# UltrasonicSensor.net
KiCad netlist of a schematic drawn in EAGLE
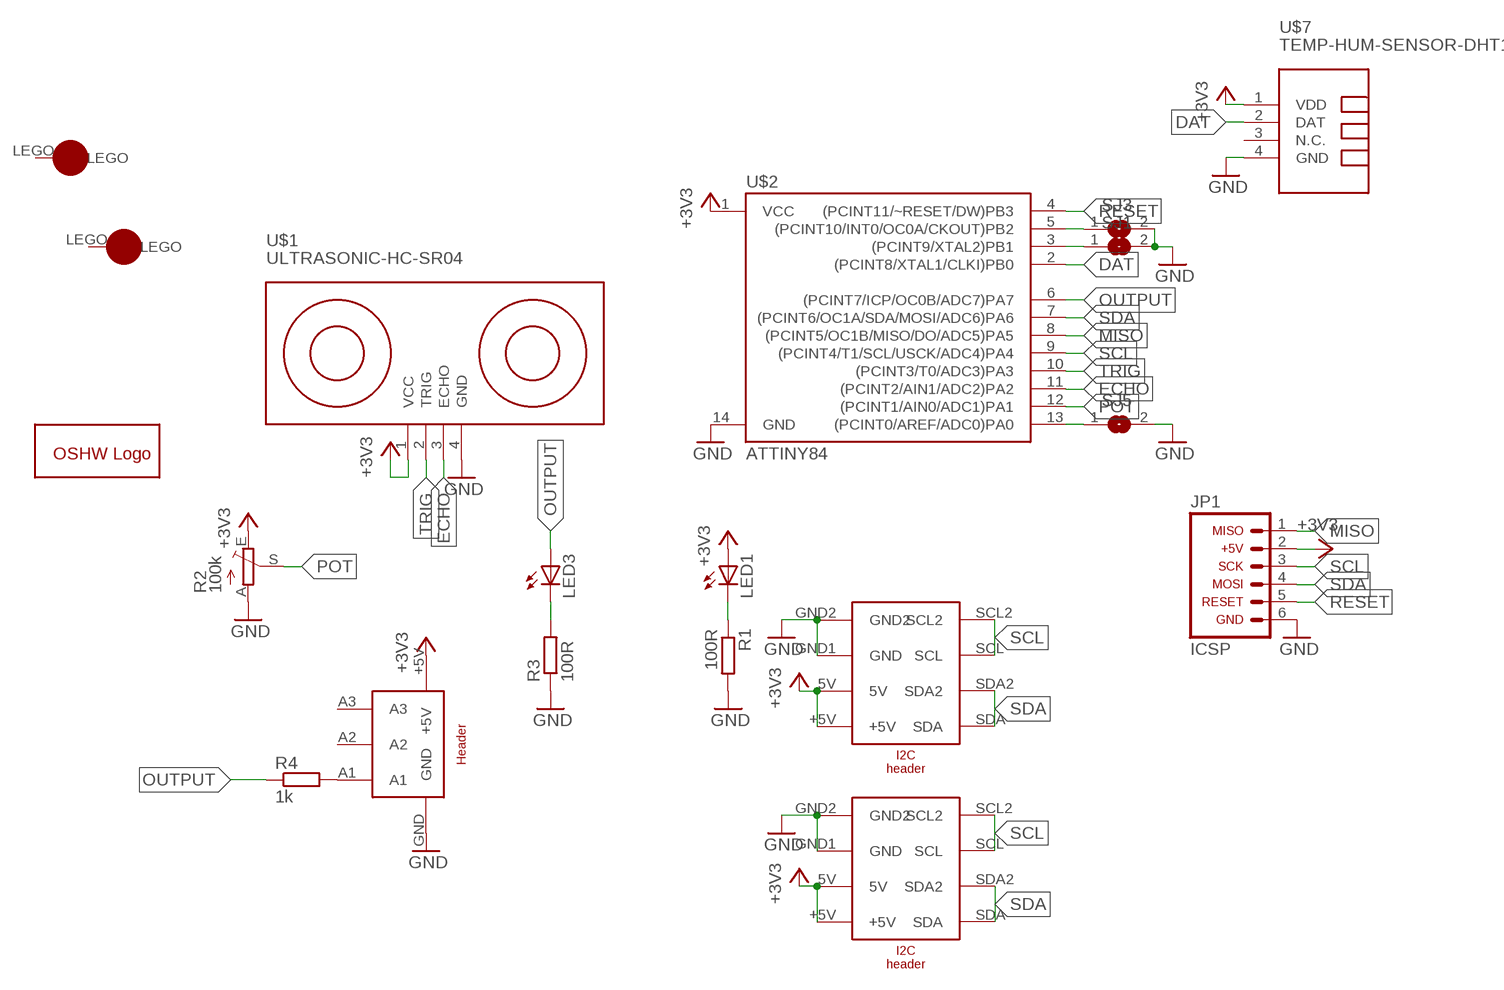
[diagram p0: schematic, sheet 1]

(export (version "E")
  (design (tool "Eeschema 10.0.6"))
  (components
    (comp (ref "JP1")
      (value "ICSP_HEADER")
      (footprint "eagle-import:ICSP_HEADER")
      (libsource (lib "eagle-import") (part "ICSP_HEADER"))
    )
    (comp (ref "LED1")
      (value "LEDCHIPLED_1206")
      (footprint "eagle-import:CHIPLED_1206")
      (libsource (lib "eagle-import") (part "LEDCHIPLED_1206"))
    )
    (comp (ref "LED3")
      (value "LEDCHIPLED_1206")
      (footprint "eagle-import:CHIPLED_1206")
      (libsource (lib "eagle-import") (part "LEDCHIPLED_1206"))
    )
    (comp (ref "R1")
      (value "100R")
      (footprint "eagle-import:M1206")
      (libsource (lib "eagle-import") (part "R-EU_M1206"))
    )
    (comp (ref "R2")
      (value "100k")
      (footprint "eagle-import:B64Y")
      (libsource (lib "eagle-import") (part "TRIM_EU-B64Y"))
    )
    (comp (ref "R3")
      (value "100R")
      (footprint "eagle-import:M1206")
      (libsource (lib "eagle-import") (part "R-EU_M1206"))
    )
    (comp (ref "R4")
      (value "1k")
      (footprint "eagle-import:M1206")
      (libsource (lib "eagle-import") (part "R-EU_M1206"))
    )
    (comp (ref "SJ1") (value "SJ") (footprint "eagle-import:SJ") (libsource (lib "eagle-import") (part "SJ")))
    (comp (ref "SJ3") (value "SJ") (footprint "eagle-import:SJ") (libsource (lib "eagle-import") (part "SJ")))
    (comp (ref "SJ5") (value "SJ") (footprint "eagle-import:SJ") (libsource (lib "eagle-import") (part "SJ")))
    (comp (ref "U$1")
      (value "ULTRASONIC-HC-SR04")
      (footprint "eagle-import:ULTRASONIC-HC-SR04")
      (libsource (lib "eagle-import") (part "ULTRASONIC-HC-SR04"))
    )
    (comp (ref "U$2")
      (value "ATTINY84")
      (footprint "eagle-import:SO14")
      (libsource (lib "eagle-import") (part "ATTINY84"))
    )
    (comp (ref "U$3")
      (value "I2C_HEADER")
      (footprint "eagle-import:I2_HEADER")
      (libsource (lib "eagle-import") (part "I2C_HEADER"))
    )
    (comp (ref "U$4")
      (value "I2C_HEADER")
      (footprint "eagle-import:I2_HEADER")
      (libsource (lib "eagle-import") (part "I2C_HEADER"))
    )
    (comp (ref "U$5")
      (value "OPENSOURCE")
      (footprint "eagle-import:OSHW_5MM")
      (libsource (lib "eagle-import") (part "OPENSOURCE"))
    )
    (comp (ref "U$6")
      (value "CONNECTOR_1X5")
      (footprint "eagle-import:CONNECTOR_1X5")
      (libsource (lib "eagle-import") (part "CONNECTOR_1X5"))
    )
    (comp (ref "U$7")
      (value "TEMP-HUM-SENSOR-DHT11")
      (footprint "eagle-import:TEMP-HUM-SENSOR-DHT11")
      (libsource (lib "eagle-import") (part "TEMP-HUM-SENSOR-DHT11"))
    )
    (comp (ref "U$8")
      (value "LEGO-1X1")
      (footprint "eagle-import:LEGO-1X1")
      (libsource (lib "eagle-import") (part "LEGO-1X1"))
    )
    (comp (ref "U$9")
      (value "LEGO-1X1")
      (footprint "eagle-import:LEGO-1X1")
      (libsource (lib "eagle-import") (part "LEGO-1X1"))
    )
  )
  (nets
    (net (code "1") (name "+3V3") (class "Default")
      (node (ref "JP1") (pin "2") (pinfunction "2_2") (pintype "passive"))
      (node (ref "LED1") (pin "A") (pinfunction "A_A") (pintype "passive"))
      (node (ref "R2") (pin "E") (pinfunction "E_E") (pintype "passive"))
      (node (ref "U$1") (pin "1") (pinfunction "VCC_1") (pintype "power_in"))
      (node (ref "U$2") (pin "1") (pinfunction "VCC_1") (pintype "bidirectional"))
      (node (ref "U$3") (pin "+5V") (pinfunction "+5V_+5V") (pintype "bidirectional"))
      (node (ref "U$3") (pin "5V") (pinfunction "5V_5V") (pintype "bidirectional"))
      (node (ref "U$4") (pin "+5V") (pinfunction "+5V_+5V") (pintype "bidirectional"))
      (node (ref "U$4") (pin "5V") (pinfunction "5V_5V") (pintype "bidirectional"))
      (node (ref "U$6") (pin "+5V") (pinfunction "+5V_+5V") (pintype "bidirectional"))
      (node (ref "U$7") (pin "1") (pinfunction "VDD_1") (pintype "power_in"))
    )
    (net (code "2") (name "DAT") (class "Default")
      (node (ref "U$2") (pin "2") (pinfunction "(PCINT8/XTAL1/CLKI)PB0_2") (pintype "bidirectional"))
      (node (ref "U$7") (pin "2") (pinfunction "DAT_2") (pintype "bidirectional"))
    )
    (net (code "3") (name "ECHO") (class "Default")
      (node (ref "U$1") (pin "3") (pinfunction "ECHO_3") (pintype "output"))
      (node (ref "U$2") (pin "11") (pinfunction "(PCINT2/AIN1/ADC2)PA2_11") (pintype "bidirectional"))
    )
    (net (code "4") (name "GND") (class "Default")
      (node (ref "JP1") (pin "6") (pinfunction "6_6") (pintype "passive"))
      (node (ref "R1") (pin "2") (pinfunction "2_2") (pintype "passive"))
      (node (ref "R2") (pin "A") (pinfunction "A_A") (pintype "passive"))
      (node (ref "R3") (pin "1") (pinfunction "1_1") (pintype "passive"))
      (node (ref "SJ1") (pin "2") (pinfunction "2_2") (pintype "passive"))
      (node (ref "SJ3") (pin "2") (pinfunction "2_2") (pintype "passive"))
      (node (ref "SJ5") (pin "2") (pinfunction "2_2") (pintype "passive"))
      (node (ref "U$1") (pin "4") (pinfunction "GND_4") (pintype "power_in"))
      (node (ref "U$2") (pin "14") (pinfunction "GND_14") (pintype "bidirectional"))
      (node (ref "U$3") (pin "GND1") (pinfunction "GND_GND1") (pintype "bidirectional"))
      (node (ref "U$3") (pin "GND2") (pinfunction "GND2_GND2") (pintype "bidirectional"))
      (node (ref "U$4") (pin "GND1") (pinfunction "GND_GND1") (pintype "bidirectional"))
      (node (ref "U$4") (pin "GND2") (pinfunction "GND2_GND2") (pintype "bidirectional"))
      (node (ref "U$6") (pin "GND") (pinfunction "GND_GND") (pintype "bidirectional"))
      (node (ref "U$7") (pin "4") (pinfunction "GND_4") (pintype "power_in"))
    )
    (net (code "5") (name "MISO") (class "Default")
      (node (ref "JP1") (pin "1") (pinfunction "1_1") (pintype "passive"))
      (node (ref "U$2") (pin "8") (pinfunction "(PCINT5/OC1B/MISO/DO/ADC5)PA5_8") (pintype "bidirectional"))
    )
    (net (code "6") (name "Net-(LED1-PadC)") (class "Default")
      (node (ref "LED1") (pin "C") (pinfunction "C_C") (pintype "passive"))
      (node (ref "R1") (pin "1") (pinfunction "1_1") (pintype "passive"))
    )
    (net (code "7") (name "Net-(LED3-PadC)") (class "Default")
      (node (ref "LED3") (pin "C") (pinfunction "C_C") (pintype "passive"))
      (node (ref "R3") (pin "2") (pinfunction "2_2") (pintype "passive"))
    )
    (net (code "8") (name "Net-(R4-Pad2)") (class "Default")
      (node (ref "R4") (pin "2") (pinfunction "2_2") (pintype "passive"))
      (node (ref "U$6") (pin "A1") (pinfunction "A1_A1") (pintype "bidirectional"))
    )
    (net (code "9") (name "Net-(U$2-(PCINT0{slash}AREF{slash}ADC0)PA0)") (class "Default")
      (node (ref "SJ5") (pin "1") (pinfunction "1_1") (pintype "passive"))
      (node (ref "U$2") (pin "13") (pinfunction "(PCINT0/AREF/ADC0)PA0_13") (pintype "bidirectional"))
    )
    (net (code "10") (name "Net-(U$2-(PCINT9{slash}XTAL2)PB1)") (class "Default")
      (node (ref "SJ1") (pin "1") (pinfunction "1_1") (pintype "passive"))
      (node (ref "U$2") (pin "3") (pinfunction "(PCINT9/XTAL2)PB1_3") (pintype "bidirectional"))
    )
    (net (code "11") (name "Net-(U$2-(PCINT10{slash}INT0{slash}OC0A{slash}CKOUT)PB2)") (class "Default")
      (node (ref "SJ3") (pin "1") (pinfunction "1_1") (pintype "passive"))
      (node (ref "U$2") (pin "5") (pinfunction "(PCINT10/INT0/OC0A/CKOUT)PB2_5") (pintype "bidirectional"))
    )
    (net (code "12") (name "OUTPUT") (class "Default")
      (node (ref "LED3") (pin "A") (pinfunction "A_A") (pintype "passive"))
      (node (ref "R4") (pin "1") (pinfunction "1_1") (pintype "passive"))
      (node (ref "U$2") (pin "6") (pinfunction "(PCINT7/ICP/OC0B/ADC7)PA7_6") (pintype "bidirectional"))
    )
    (net (code "13") (name "POT") (class "Default")
      (node (ref "R2") (pin "S") (pinfunction "S_S") (pintype "passive"))
      (node (ref "U$2") (pin "12") (pinfunction "(PCINT1/AIN0/ADC1)PA1_12") (pintype "bidirectional"))
    )
    (net (code "14") (name "RESET") (class "Default")
      (node (ref "JP1") (pin "5") (pinfunction "5_5") (pintype "passive"))
      (node (ref "U$2") (pin "4") (pinfunction "(PCINT11/~{RESET/DW})PB3_4") (pintype "bidirectional"))
    )
    (net (code "15") (name "SCL") (class "Default")
      (node (ref "JP1") (pin "3") (pinfunction "3_3") (pintype "passive"))
      (node (ref "U$2") (pin "9") (pinfunction "(PCINT4/T1/SCL/USCK/ADC4)PA4_9") (pintype "bidirectional"))
      (node (ref "U$3") (pin "SCL") (pinfunction "SCL_SCL") (pintype "bidirectional"))
      (node (ref "U$3") (pin "SCL2") (pinfunction "SCL2_SCL2") (pintype "bidirectional"))
      (node (ref "U$4") (pin "SCL") (pinfunction "SCL_SCL") (pintype "bidirectional"))
      (node (ref "U$4") (pin "SCL2") (pinfunction "SCL2_SCL2") (pintype "bidirectional"))
    )
    (net (code "16") (name "SDA") (class "Default")
      (node (ref "JP1") (pin "4") (pinfunction "4_4") (pintype "passive"))
      (node (ref "U$2") (pin "7") (pinfunction "(PCINT6/OC1A/SDA/MOSI/ADC6)PA6_7") (pintype "bidirectional"))
      (node (ref "U$3") (pin "SDA") (pinfunction "SDA_SDA") (pintype "bidirectional"))
      (node (ref "U$3") (pin "SDA2") (pinfunction "SDA2_SDA2") (pintype "bidirectional"))
      (node (ref "U$4") (pin "SDA") (pinfunction "SDA_SDA") (pintype "bidirectional"))
      (node (ref "U$4") (pin "SDA2") (pinfunction "SDA2_SDA2") (pintype "bidirectional"))
    )
    (net (code "17") (name "TRIG") (class "Default")
      (node (ref "U$1") (pin "2") (pinfunction "TRIG_2") (pintype "input"))
      (node (ref "U$2") (pin "10") (pinfunction "(PCINT3/T0/ADC3)PA3_10") (pintype "bidirectional"))
    )
    (net (code "18") (name "unconnected-(U$6-PadA2)") (class "Default")
      (node (ref "U$6") (pin "A2") (pinfunction "A2_A2") (pintype "bidirectional"))
    )
    (net (code "19") (name "unconnected-(U$6-PadA3)") (class "Default")
      (node (ref "U$6") (pin "A3") (pinfunction "A3_A3") (pintype "bidirectional"))
    )
    (net (code "20") (name "unconnected-(U$7-N.C.-Pad3)") (class "Default")
      (node (ref "U$7") (pin "3") (pinfunction "N.C._3") (pintype "passive"))
    )
    (net (code "21") (name "unconnected-(U$8-PadLEGO)") (class "Default")
      (node (ref "U$8") (pin "LEGO") (pinfunction "LEGO_LEGO") (pintype "bidirectional"))
    )
    (net (code "22") (name "unconnected-(U$9-PadLEGO)") (class "Default")
      (node (ref "U$9") (pin "LEGO") (pinfunction "LEGO_LEGO") (pintype "bidirectional"))
    )
  )
)
